# LCCAtmegaXXM1_2.net
KiCad netlist of a schematic drawn in Altium Designer
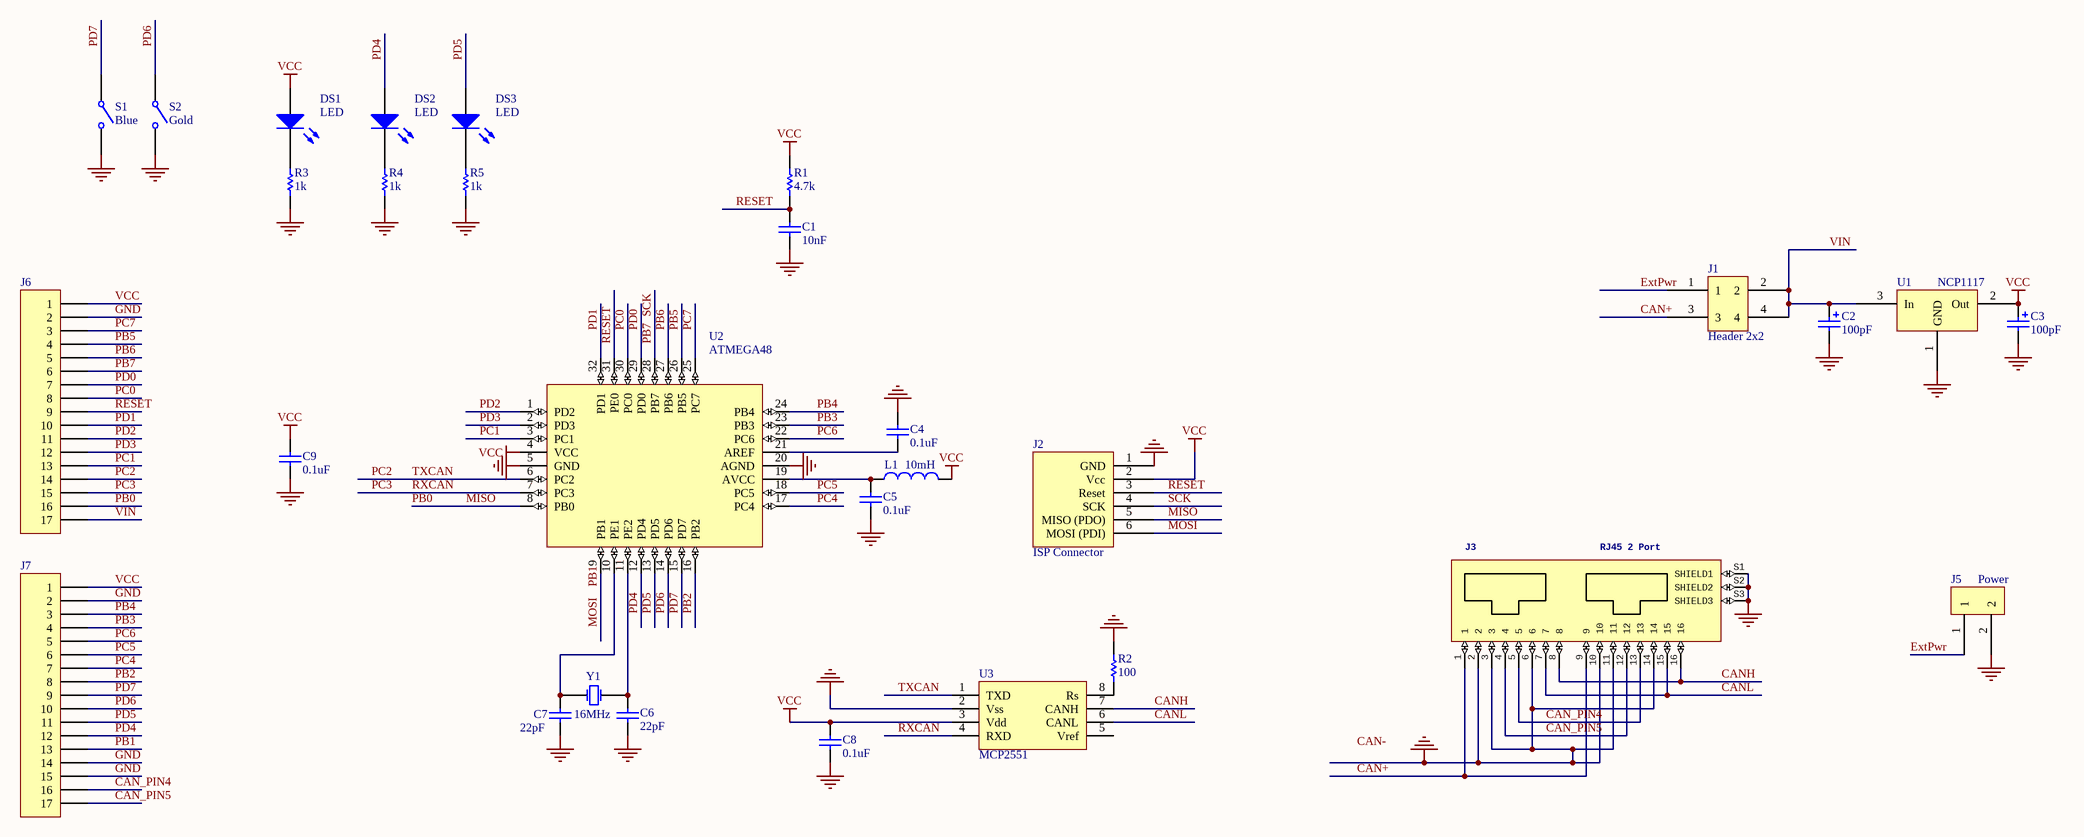
[diagram p0: LCCAtmegaXXM1.2.SchDoc]

(export (version "E")
  (design (tool "Eeschema 10.0.6"))
  (components
    (comp (ref "C1")
      (value "10nF")
      (footprint "Cap SMD 0805A")
      (description "Capacitor")
      (fields (field (name "Comment") "Cap") (field (name "PUBLISHER") "Altium Limited"))
      (libsource (lib "Custom") (part "Cap"))
    )
    (comp (ref "C2")
      (value "100pF")
      (footprint "Cap SMD Elect 5x5.3")
      (description "Polarized Capacitor (Radial)")
      (fields (field (name "Comment") "Cap Pol") (field (name "PUBLISHER") "Altium Limited"))
      (libsource (lib "Custom") (part "Cap Pol"))
    )
    (comp (ref "C3")
      (value "100pF")
      (footprint "Cap SMD Elect 5x5.3")
      (description "Polarized Capacitor (Radial)")
      (fields (field (name "Comment") "Cap Pol") (field (name "PUBLISHER") "Altium Limited"))
      (libsource (lib "Custom") (part "Cap Pol"))
    )
    (comp (ref "C4")
      (value "0.1uF")
      (footprint "Cap SMD 0805A")
      (description "Capacitor")
      (fields (field (name "Comment") "Cap") (field (name "PUBLISHER") "Altium Limited"))
      (libsource (lib "Custom") (part "Cap"))
    )
    (comp (ref "C5")
      (value "0.1uF")
      (footprint "Cap SMD 0805A")
      (description "Capacitor")
      (fields (field (name "Comment") "Cap") (field (name "PUBLISHER") "Altium Limited"))
      (libsource (lib "Custom") (part "Cap"))
    )
    (comp (ref "C6")
      (value "22pF")
      (footprint "Cap SMD 0805A")
      (description "Capacitor")
      (fields (field (name "Comment") "Cap") (field (name "PUBLISHER") "Altium Limited"))
      (libsource (lib "Custom") (part "Cap"))
    )
    (comp (ref "C7")
      (value "22pF")
      (footprint "Cap SMD 0805A")
      (description "Capacitor")
      (fields (field (name "Comment") "Cap") (field (name "PUBLISHER") "Altium Limited"))
      (libsource (lib "Custom") (part "Cap"))
    )
    (comp (ref "C8")
      (value "0.1uF")
      (footprint "Cap SMD 0805A")
      (description "Capacitor")
      (fields (field (name "Comment") "Cap") (field (name "PUBLISHER") "Altium Limited"))
      (libsource (lib "Custom") (part "Cap"))
    )
    (comp (ref "C9")
      (value "0.1uF")
      (footprint "Cap SMD 0805A")
      (description "Capacitor")
      (fields (field (name "Comment") "Cap") (field (name "PUBLISHER") "Altium Limited"))
      (libsource (lib "Custom") (part "Cap"))
    )
    (comp (ref "DS1")
      (value "LED")
      (footprint "LED SMD 0805")
      (description "RGB LED Common Anode")
      (fields (field (name "PUBLISHER") "Altium Limited"))
      (libsource (lib "Custom") (part "LED"))
    )
    (comp (ref "DS2")
      (value "LED")
      (footprint "LED SMD 0805")
      (description "RGB LED Common Anode")
      (fields (field (name "PUBLISHER") "Altium Limited"))
      (libsource (lib "Custom") (part "LED"))
    )
    (comp (ref "DS3")
      (value "LED")
      (footprint "LED SMD 0805")
      (description "RGB LED Common Anode")
      (fields (field (name "PUBLISHER") "Altium Limited"))
      (libsource (lib "Custom") (part "LED"))
    )
    (comp (ref "J1") (value "Header 2x2") (footprint "HDR2x2") (libsource (lib "Custom") (part "HDR2x2")))
    (comp (ref "J2")
      (value "ISP Connector")
      (footprint "PcbLib1:HDR2x3")
      (libsource (lib "Custom") (part "ISP Connector"))
    )
    (comp (ref "J3")
      (value "RJ45 2 Port")
      (footprint "432238128")
      (fields
        (field (name "MOUSER_PART_NUMBER") "538-43223-8128")
        (field (name "MANUFACTURER_PART_NUMBER") "43223-8128")
      )
      (libsource (lib "Custom") (part "43223-8128_1"))
    )
    (comp (ref "J5")
      (value "Power")
      (footprint "DC 2.5mm PCB Jack")
      (libsource (lib "Custom") (part "SIP2 CONNECTOR"))
    )
    (comp (ref "J6")
      (value "Header 17")
      (footprint "HDR1X17")
      (description "Header, 17-Pin")
      (fields (field (name "PUBLISHER") "Altium Limited"))
      (libsource (lib "Miscellaneous Connectors") (part "Header 17"))
    )
    (comp (ref "J7")
      (value "Header 17")
      (footprint "HDR1X17")
      (description "Header, 17-Pin")
      (fields (field (name "PUBLISHER") "Altium Limited"))
      (libsource (lib "Miscellaneous Connectors") (part "Header 17"))
    )
    (comp (ref "L1")
      (value "10mH")
      (footprint "Cap SMD 0805A")
      (description "Inductor")
      (fields (field (name "PUBLISHER") "Altium Limited"))
      (libsource (lib "Miscellaneous Devices") (part "Inductor"))
    )
    (comp (ref "R1")
      (value "4.7k")
      (footprint "Res SMD 0805A")
      (fields (field (name "Comment") "Res1"))
      (libsource (lib "Custom") (part "Resistor"))
    )
    (comp (ref "R2")
      (value "100")
      (footprint "Res SMD 0805A")
      (fields (field (name "Comment") "Res1"))
      (libsource (lib "Custom") (part "Resistor"))
    )
    (comp (ref "R3")
      (value "1k")
      (footprint "Res SMD 0805A")
      (fields (field (name "Comment") "Res1"))
      (libsource (lib "Custom") (part "Resistor"))
    )
    (comp (ref "R4")
      (value "1k")
      (footprint "Res SMD 0805A")
      (fields (field (name "Comment") "Res1"))
      (libsource (lib "Custom") (part "Resistor"))
    )
    (comp (ref "R5")
      (value "1k")
      (footprint "Res SMD 0805A")
      (fields (field (name "Comment") "Res1"))
      (libsource (lib "Custom") (part "Resistor"))
    )
    (comp (ref "S1")
      (value "Blue")
      (footprint "SPST Tactile 6x3.5")
      (description "Push Button, Single-Pole, Single-Throw")
      (fields (field (name "PUBLISHER") "Altium Limited"))
      (libsource (lib "Custom") (part "SW-PB-SPST"))
    )
    (comp (ref "S2")
      (value "Gold")
      (footprint "SPST Tactile 6x3.5")
      (description "Push Button, Single-Pole, Single-Throw")
      (fields (field (name "PUBLISHER") "Altium Limited"))
      (libsource (lib "Custom") (part "SW-PB-SPST"))
    )
    (comp (ref "U1")
      (value "NCP1117")
      (footprint "SOT-223")
      (description "LDO Regulator")
      (libsource (lib "Custom") (part "NCP1117"))
    )
    (comp (ref "U2")
      (value "ATMEGA48")
      (footprint "TQFP32")
      (description "8-Bit AVR Microcontroller")
      (fields (field (name "PUBLISHER") "Altium Limited"))
      (libsource (lib "Custom") (part "ATMEGA64M1"))
    )
    (comp (ref "U3")
      (value "MCP2551")
      (footprint "SOIC8")
      (description "MCP2551 High Speed CAN Transceiver")
      (libsource (lib "Custom") (part "MCP2551"))
    )
    (comp (ref "Y1")
      (value "16MHz")
      (footprint "Crystal TXC SMD")
      (description "Crystal Oscillator")
      (fields (field (name "PUBLISHER") "Altium Limited"))
      (libsource (lib "Miscellaneous Devices") (part "XTAL"))
    )
  )
  (nets
    (net (code "1") (name "/CAN+") (class "Default")
      (node (ref "J1") (pin "3") (pinfunction "3_3") (pintype "passive"))
      (node (ref "J3") (pin "1") (pinfunction "1_1") (pintype "bidirectional"))
      (node (ref "J3") (pin "9") (pinfunction "9_9") (pintype "bidirectional"))
    )
    (net (code "3") (name "/CANH") (class "Default")
      (node (ref "J3") (pin "16") (pinfunction "16_16") (pintype "bidirectional"))
      (node (ref "J3") (pin "8") (pinfunction "8_8") (pintype "bidirectional"))
      (node (ref "U3") (pin "7") (pinfunction "CANH_7") (pintype "passive"))
    )
    (net (code "4") (name "/CANL") (class "Default")
      (node (ref "J3") (pin "15") (pinfunction "15_15") (pintype "bidirectional"))
      (node (ref "J3") (pin "7") (pinfunction "7_7") (pintype "bidirectional"))
      (node (ref "U3") (pin "6") (pinfunction "CANL_6") (pintype "passive"))
    )
    (net (code "5") (name "/CAN_PIN4") (class "Default")
      (node (ref "J3") (pin "13") (pinfunction "13_13") (pintype "bidirectional"))
      (node (ref "J3") (pin "5") (pinfunction "5_5") (pintype "bidirectional"))
      (node (ref "J7") (pin "16") (pinfunction "16_16") (pintype "passive"))
    )
    (net (code "6") (name "/CAN_PIN5") (class "Default")
      (node (ref "J3") (pin "12") (pinfunction "12_12") (pintype "bidirectional"))
      (node (ref "J3") (pin "4") (pinfunction "4_4") (pintype "bidirectional"))
      (node (ref "J7") (pin "17") (pinfunction "17_17") (pintype "passive"))
    )
    (net (code "7") (name "/ExtPwr") (class "Default")
      (node (ref "J1") (pin "1") (pinfunction "1_1") (pintype "passive"))
      (node (ref "J5") (pin "1") (pinfunction "1_1") (pintype "passive"))
    )
    (net (code "8") (name "/MISO") (class "Default")
      (node (ref "J2") (pin "5") (pinfunction "MISO_(PDO)_5") (pintype "passive"))
      (node (ref "J6") (pin "16") (pinfunction "16_16") (pintype "passive"))
      (node (ref "U2") (pin "8") (pinfunction "PB0_8") (pintype "bidirectional"))
    )
    (net (code "9") (name "/MOSI") (class "Default")
      (node (ref "J2") (pin "6") (pinfunction "MOSI_(PDI)_6") (pintype "passive"))
      (node (ref "J7") (pin "13") (pinfunction "13_13") (pintype "passive"))
      (node (ref "U2") (pin "9") (pinfunction "PB1_9") (pintype "bidirectional"))
    )
    (net (code "10") (name "/PB2") (class "Default")
      (node (ref "J7") (pin "8") (pinfunction "8_8") (pintype "passive"))
      (node (ref "U2") (pin "16") (pinfunction "PB2_16") (pintype "bidirectional"))
    )
    (net (code "11") (name "/PB3") (class "Default")
      (node (ref "J7") (pin "4") (pinfunction "4_4") (pintype "passive"))
      (node (ref "U2") (pin "23") (pinfunction "PB3_23") (pintype "bidirectional"))
    )
    (net (code "12") (name "/PB4") (class "Default")
      (node (ref "J7") (pin "3") (pinfunction "3_3") (pintype "passive"))
      (node (ref "U2") (pin "24") (pinfunction "PB4_24") (pintype "bidirectional"))
    )
    (net (code "13") (name "/PB5") (class "Default")
      (node (ref "J6") (pin "4") (pinfunction "4_4") (pintype "passive"))
      (node (ref "U2") (pin "26") (pinfunction "PB5_26") (pintype "bidirectional"))
    )
    (net (code "14") (name "/PB6") (class "Default")
      (node (ref "J6") (pin "5") (pinfunction "5_5") (pintype "passive"))
      (node (ref "U2") (pin "27") (pinfunction "PB6_27") (pintype "bidirectional"))
    )
    (net (code "15") (name "/PB7") (class "Default")
      (node (ref "J2") (pin "4") (pinfunction "SCK_4") (pintype "passive"))
      (node (ref "J6") (pin "6") (pinfunction "6_6") (pintype "passive"))
      (node (ref "U2") (pin "28") (pinfunction "PB7_28") (pintype "bidirectional"))
    )
    (net (code "16") (name "/PC0") (class "Default")
      (node (ref "J6") (pin "8") (pinfunction "8_8") (pintype "passive"))
      (node (ref "U2") (pin "30") (pinfunction "PC0_30") (pintype "bidirectional"))
    )
    (net (code "17") (name "/PC1") (class "Default")
      (node (ref "J6") (pin "13") (pinfunction "13_13") (pintype "passive"))
      (node (ref "U2") (pin "3") (pinfunction "PC1_3") (pintype "bidirectional"))
    )
    (net (code "18") (name "/PC2") (class "Default")
      (node (ref "J6") (pin "14") (pinfunction "14_14") (pintype "passive"))
      (node (ref "U2") (pin "6") (pinfunction "PC2_6") (pintype "bidirectional"))
      (node (ref "U3") (pin "1") (pinfunction "TXD_1") (pintype "passive"))
    )
    (net (code "19") (name "/PC3") (class "Default")
      (node (ref "J6") (pin "15") (pinfunction "15_15") (pintype "passive"))
      (node (ref "U2") (pin "7") (pinfunction "PC3_7") (pintype "bidirectional"))
      (node (ref "U3") (pin "4") (pinfunction "RXD_4") (pintype "passive"))
    )
    (net (code "20") (name "/PC4") (class "Default")
      (node (ref "J7") (pin "7") (pinfunction "7_7") (pintype "passive"))
      (node (ref "U2") (pin "17") (pinfunction "PC4_17") (pintype "bidirectional"))
    )
    (net (code "21") (name "/PC5") (class "Default")
      (node (ref "J7") (pin "6") (pinfunction "6_6") (pintype "passive"))
      (node (ref "U2") (pin "18") (pinfunction "PC5_18") (pintype "bidirectional"))
    )
    (net (code "22") (name "/PC6") (class "Default")
      (node (ref "J7") (pin "5") (pinfunction "5_5") (pintype "passive"))
      (node (ref "U2") (pin "22") (pinfunction "PC6_22") (pintype "bidirectional"))
    )
    (net (code "23") (name "/PC7") (class "Default")
      (node (ref "J6") (pin "3") (pinfunction "3_3") (pintype "passive"))
      (node (ref "U2") (pin "25") (pinfunction "PC7_25") (pintype "bidirectional"))
    )
    (net (code "24") (name "/PD0") (class "Default")
      (node (ref "J6") (pin "7") (pinfunction "7_7") (pintype "passive"))
      (node (ref "U2") (pin "29") (pinfunction "PD0_29") (pintype "bidirectional"))
    )
    (net (code "25") (name "/PD1") (class "Default")
      (node (ref "J6") (pin "10") (pinfunction "10_10") (pintype "passive"))
      (node (ref "U2") (pin "32") (pinfunction "PD1_32") (pintype "bidirectional"))
    )
    (net (code "26") (name "/PD2") (class "Default")
      (node (ref "J6") (pin "11") (pinfunction "11_11") (pintype "passive"))
      (node (ref "U2") (pin "1") (pinfunction "PD2_1") (pintype "bidirectional"))
    )
    (net (code "27") (name "/PD3") (class "Default")
      (node (ref "J6") (pin "12") (pinfunction "12_12") (pintype "passive"))
      (node (ref "U2") (pin "2") (pinfunction "PD3_2") (pintype "bidirectional"))
    )
    (net (code "28") (name "/PD4") (class "Default")
      (node (ref "DS2") (pin "A") (pinfunction "A_A") (pintype "passive"))
      (node (ref "J7") (pin "12") (pinfunction "12_12") (pintype "passive"))
      (node (ref "U2") (pin "12") (pinfunction "PD4_12") (pintype "bidirectional"))
    )
    (net (code "29") (name "/PD5") (class "Default")
      (node (ref "DS3") (pin "A") (pinfunction "A_A") (pintype "passive"))
      (node (ref "J7") (pin "11") (pinfunction "11_11") (pintype "passive"))
      (node (ref "U2") (pin "13") (pinfunction "PD5_13") (pintype "bidirectional"))
    )
    (net (code "30") (name "/PD6") (class "Default")
      (node (ref "J7") (pin "10") (pinfunction "10_10") (pintype "passive"))
      (node (ref "S2") (pin "1") (pinfunction "1_1") (pintype "passive"))
      (node (ref "U2") (pin "14") (pinfunction "PD6_14") (pintype "bidirectional"))
    )
    (net (code "31") (name "/PD7") (class "Default")
      (node (ref "J7") (pin "9") (pinfunction "9_9") (pintype "passive"))
      (node (ref "S1") (pin "1") (pinfunction "1_1") (pintype "passive"))
      (node (ref "U2") (pin "15") (pinfunction "PD7_15") (pintype "bidirectional"))
    )
    (net (code "32") (name "/RESET") (class "Default")
      (node (ref "C1") (pin "1") (pinfunction "1_1") (pintype "passive"))
      (node (ref "J2") (pin "3") (pinfunction "Reset_3") (pintype "passive"))
      (node (ref "J6") (pin "9") (pinfunction "9_9") (pintype "passive"))
      (node (ref "R1") (pin "1") (pinfunction "1_1") (pintype "passive"))
      (node (ref "U2") (pin "31") (pinfunction "PE0_31") (pintype "bidirectional"))
    )
    (net (code "33") (name "/VIN") (class "Default")
      (node (ref "C2") (pin "1") (pinfunction "1_1") (pintype "passive"))
      (node (ref "J1") (pin "2") (pinfunction "2_2") (pintype "passive"))
      (node (ref "J1") (pin "4") (pinfunction "4_4") (pintype "passive"))
      (node (ref "J6") (pin "17") (pinfunction "17_17") (pintype "passive"))
      (node (ref "U1") (pin "3") (pinfunction "In_3") (pintype "passive"))
    )
    (net (code "34") (name "GND") (class "Default")
      (node (ref "C1") (pin "2") (pinfunction "2_2") (pintype "passive"))
      (node (ref "C2") (pin "2") (pinfunction "2_2") (pintype "passive"))
      (node (ref "C3") (pin "2") (pinfunction "2_2") (pintype "passive"))
      (node (ref "C4") (pin "2") (pinfunction "2_2") (pintype "passive"))
      (node (ref "C5") (pin "2") (pinfunction "2_2") (pintype "passive"))
      (node (ref "C6") (pin "1") (pinfunction "1_1") (pintype "passive"))
      (node (ref "C7") (pin "1") (pinfunction "1_1") (pintype "passive"))
      (node (ref "C8") (pin "2") (pinfunction "2_2") (pintype "passive"))
      (node (ref "C9") (pin "2") (pinfunction "2_2") (pintype "passive"))
      (node (ref "J2") (pin "1") (pinfunction "GND_1") (pintype "passive"))
      (node (ref "J3") (pin "10") (pinfunction "10_10") (pintype "bidirectional"))
      (node (ref "J3") (pin "11") (pinfunction "11_11") (pintype "bidirectional"))
      (node (ref "J3") (pin "14") (pinfunction "14_14") (pintype "bidirectional"))
      (node (ref "J3") (pin "2") (pinfunction "2_2") (pintype "bidirectional"))
      (node (ref "J3") (pin "3") (pinfunction "3_3") (pintype "bidirectional"))
      (node (ref "J3") (pin "6") (pinfunction "6_6") (pintype "bidirectional"))
      (node (ref "J3") (pin "S1") (pinfunction "SHIELD1_S1") (pintype "bidirectional"))
      (node (ref "J3") (pin "S2") (pinfunction "SHIELD2_S2") (pintype "bidirectional"))
      (node (ref "J3") (pin "S3") (pinfunction "SHIELD3_S3") (pintype "bidirectional"))
      (node (ref "J5") (pin "2") (pinfunction "2_2") (pintype "passive"))
      (node (ref "J6") (pin "2") (pinfunction "2_2") (pintype "passive"))
      (node (ref "J7") (pin "14") (pinfunction "14_14") (pintype "passive"))
      (node (ref "J7") (pin "15") (pinfunction "15_15") (pintype "passive"))
      (node (ref "J7") (pin "2") (pinfunction "2_2") (pintype "passive"))
      (node (ref "R2") (pin "1") (pinfunction "1_1") (pintype "passive"))
      (node (ref "R3") (pin "1") (pinfunction "1_1") (pintype "passive"))
      (node (ref "R4") (pin "1") (pinfunction "1_1") (pintype "passive"))
      (node (ref "R5") (pin "1") (pinfunction "1_1") (pintype "passive"))
      (node (ref "S1") (pin "2") (pinfunction "2_2") (pintype "passive"))
      (node (ref "S2") (pin "2") (pinfunction "2_2") (pintype "passive"))
      (node (ref "U1") (pin "1") (pinfunction "GND_1") (pintype "passive"))
      (node (ref "U2") (pin "20") (pinfunction "AGND_20") (pintype "power_in"))
      (node (ref "U2") (pin "5") (pinfunction "GND_5") (pintype "power_in"))
      (node (ref "U3") (pin "2") (pinfunction "Vss_2") (pintype "passive"))
    )
    (net (code "35") (name "Net-(DS1-PadK)") (class "Default")
      (node (ref "DS1") (pin "K") (pinfunction "K_K") (pintype "passive"))
      (node (ref "R3") (pin "2") (pinfunction "2_2") (pintype "passive"))
    )
    (net (code "36") (name "Net-(DS2-PadK)") (class "Default")
      (node (ref "DS2") (pin "K") (pinfunction "K_K") (pintype "passive"))
      (node (ref "R4") (pin "2") (pinfunction "2_2") (pintype "passive"))
    )
    (net (code "37") (name "Net-(DS3-PadK)") (class "Default")
      (node (ref "DS3") (pin "K") (pinfunction "K_K") (pintype "passive"))
      (node (ref "R5") (pin "2") (pinfunction "2_2") (pintype "passive"))
    )
    (net (code "38") (name "Net-(U2-AREF)") (class "Default")
      (node (ref "C4") (pin "1") (pinfunction "1_1") (pintype "passive"))
      (node (ref "U2") (pin "21") (pinfunction "AREF_21") (pintype "passive"))
    )
    (net (code "39") (name "Net-(U2-AVCC)") (class "Default")
      (node (ref "C5") (pin "1") (pinfunction "1_1") (pintype "passive"))
      (node (ref "L1") (pin "1") (pinfunction "1_1") (pintype "passive"))
      (node (ref "U2") (pin "19") (pinfunction "AVCC_19") (pintype "power_in"))
    )
    (net (code "40") (name "Net-(U2-PE1)") (class "Default")
      (node (ref "C7") (pin "2") (pinfunction "2_2") (pintype "passive"))
      (node (ref "U2") (pin "10") (pinfunction "PE1_10") (pintype "bidirectional"))
      (node (ref "Y1") (pin "1") (pinfunction "OSC1_1") (pintype "passive"))
    )
    (net (code "41") (name "Net-(U2-PE2)") (class "Default")
      (node (ref "C6") (pin "2") (pinfunction "2_2") (pintype "passive"))
      (node (ref "U2") (pin "11") (pinfunction "PE2_11") (pintype "bidirectional"))
      (node (ref "Y1") (pin "2") (pinfunction "OSC2_2") (pintype "passive"))
    )
    (net (code "42") (name "Net-(U3-Rs)") (class "Default")
      (node (ref "R2") (pin "2") (pinfunction "2_2") (pintype "passive"))
      (node (ref "U3") (pin "8") (pinfunction "Rs_8") (pintype "passive"))
    )
    (net (code "43") (name "VCC") (class "Default")
      (node (ref "C3") (pin "1") (pinfunction "1_1") (pintype "passive"))
      (node (ref "C8") (pin "1") (pinfunction "1_1") (pintype "passive"))
      (node (ref "C9") (pin "1") (pinfunction "1_1") (pintype "passive"))
      (node (ref "DS1") (pin "A") (pinfunction "A_A") (pintype "passive"))
      (node (ref "J2") (pin "2") (pinfunction "Vcc_2") (pintype "passive"))
      (node (ref "J6") (pin "1") (pinfunction "1_1") (pintype "passive"))
      (node (ref "J7") (pin "1") (pinfunction "1_1") (pintype "passive"))
      (node (ref "L1") (pin "2") (pinfunction "2_2") (pintype "passive"))
      (node (ref "R1") (pin "2") (pinfunction "2_2") (pintype "passive"))
      (node (ref "U1") (pin "2") (pinfunction "Out_2") (pintype "passive"))
      (node (ref "U2") (pin "4") (pinfunction "VCC_4") (pintype "power_in"))
      (node (ref "U3") (pin "3") (pinfunction "Vdd_3") (pintype "passive"))
    )
    (net (code "44") (name "unconnected-(U3-Vref-Pad5)") (class "Default")
      (node (ref "U3") (pin "5") (pinfunction "Vref_5") (pintype "passive"))
    )
  )
)
